# minSTMc8t6.net
KiCad netlist of a schematic drawn in EasyEDA Pro
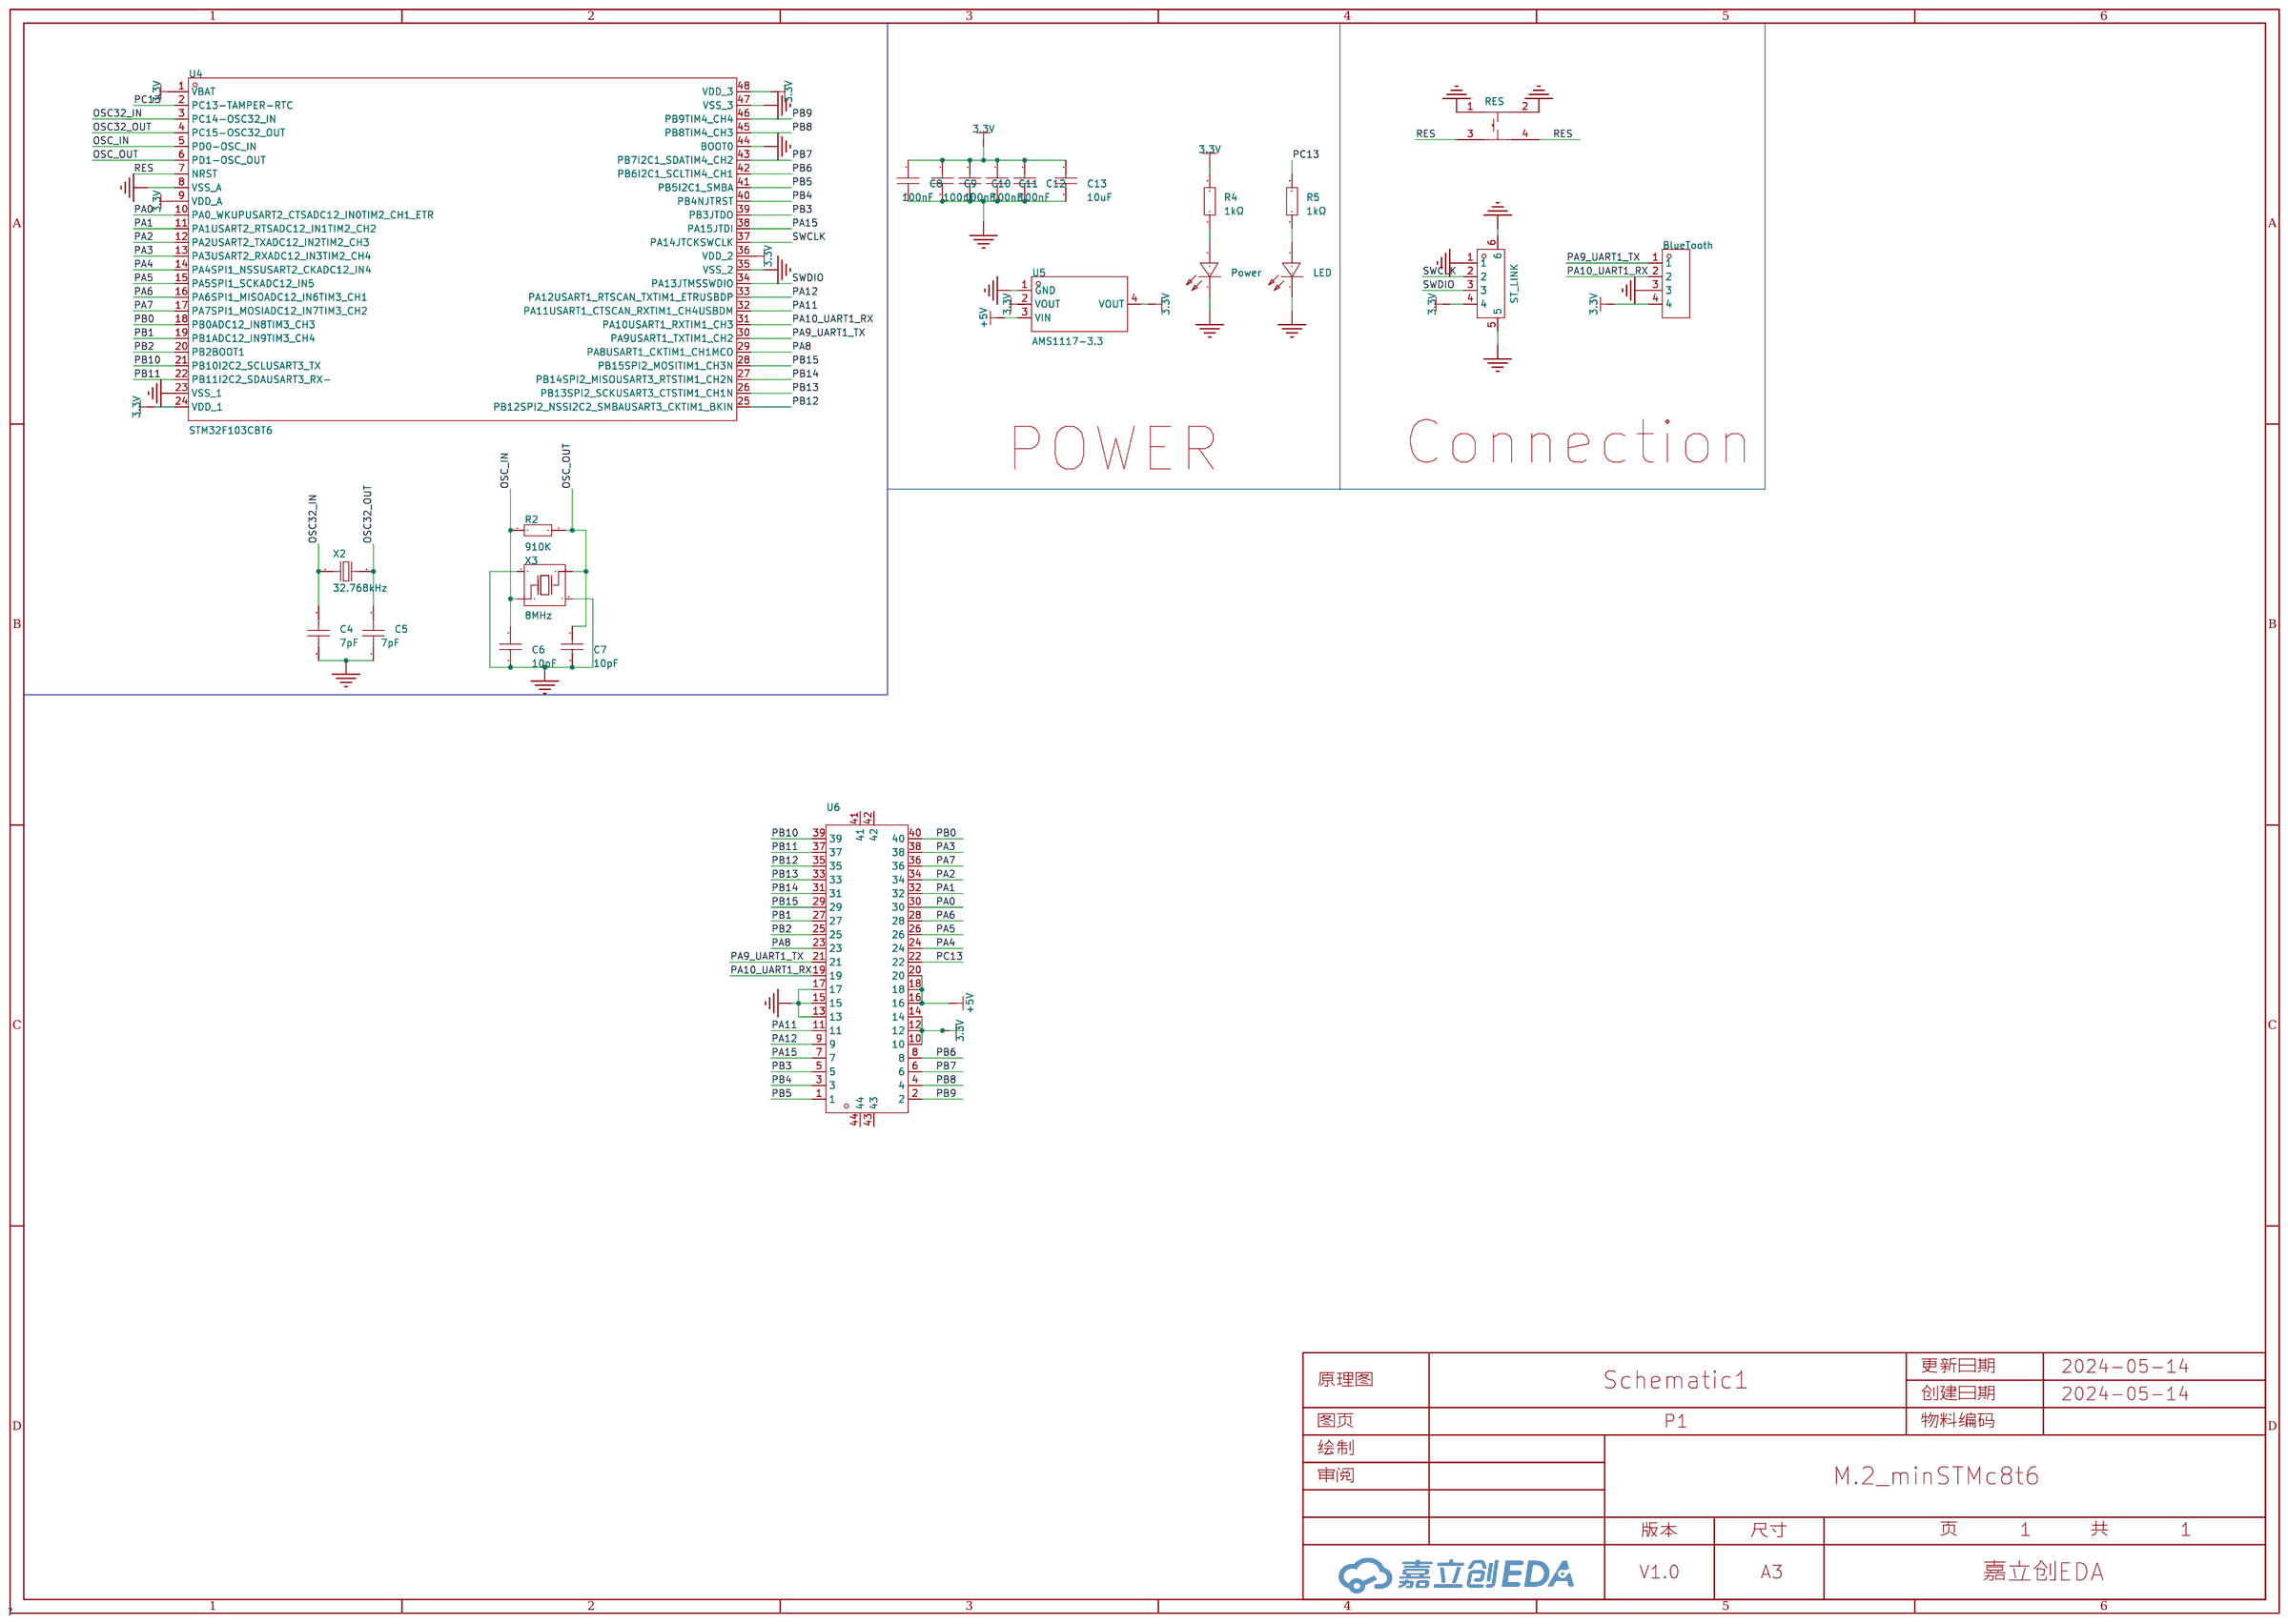
[diagram p0: schematic sheet]

(export (version "E")
  (design (tool "Eeschema 10.0.6"))
  (components
    (comp (ref "BlueTooth")
      (value "2.54-1*4P母")
      (footprint "easyedapro:HDR-TH_4P-P2.54-V-F")
      (fields (field (name "Manufacturer") "BOOMELE(博穆精密)"))
      (libsource (lib "easyedapro") (part "2.54-1*4P母"))
    )
    (comp (ref "C4")
      (value "7pF")
      (footprint "easyedapro:C0402")
      (description "容值:7pF;额定电压:50V;材质(温度系数):NP0;")
      (fields
        (field (name "Manufacturer Part") "CC0402BRNPO9BN7R0")
        (field (name "Manufacturer") "YAGEO(国巨)")
      )
      (libsource (lib "easyedapro") (part "CC0402BRNPO9BN7R0"))
    )
    (comp (ref "C5")
      (value "7pF")
      (footprint "easyedapro:C0402")
      (description "容值:7pF;额定电压:50V;材质(温度系数):NP0;")
      (fields
        (field (name "Manufacturer Part") "CC0402BRNPO9BN7R0")
        (field (name "Manufacturer") "YAGEO(国巨)")
      )
      (libsource (lib "easyedapro") (part "CC0402BRNPO9BN7R0"))
    )
    (comp (ref "C6")
      (value "10pF")
      (footprint "easyedapro:C0402")
      (description "容值:10pF;精度:±5%;额定电压:50V;材质(温度系数):NP0;")
      (fields
        (field (name "Manufacturer Part") "CC0402JRNPO9BN100")
        (field (name "Manufacturer") "YAGEO(国巨)")
      )
      (libsource (lib "easyedapro") (part "CC0402JRNPO9BN100"))
    )
    (comp (ref "C7")
      (value "10pF")
      (footprint "easyedapro:C0402")
      (description "容值:10pF;精度:±5%;额定电压:50V;材质(温度系数):NP0;")
      (fields
        (field (name "Manufacturer Part") "CC0402JRNPO9BN100")
        (field (name "Manufacturer") "YAGEO(国巨)")
      )
      (libsource (lib "easyedapro") (part "CC0402JRNPO9BN100"))
    )
    (comp (ref "C8")
      (value "100nF")
      (footprint "easyedapro:C0402")
      (description "容值:100nF;精度:±10%;额定电压:16V;材质(温度系数):X7R;")
      (fields
        (field (name "Manufacturer Part") "CL05B104KO5NNNC")
        (field (name "Manufacturer") "SAMSUNG(三星)")
      )
      (libsource (lib "easyedapro") (part "CL05B104KO5NNNC"))
    )
    (comp (ref "C9")
      (value "100nF")
      (footprint "easyedapro:C0402")
      (description "容值:100nF;精度:±10%;额定电压:16V;材质(温度系数):X7R;")
      (fields
        (field (name "Manufacturer Part") "CL05B104KO5NNNC")
        (field (name "Manufacturer") "SAMSUNG(三星)")
      )
      (libsource (lib "easyedapro") (part "CL05B104KO5NNNC"))
    )
    (comp (ref "C10")
      (value "100nF")
      (footprint "easyedapro:C0402")
      (description "容值:100nF;精度:±10%;额定电压:16V;材质(温度系数):X7R;")
      (fields
        (field (name "Manufacturer Part") "CL05B104KO5NNNC")
        (field (name "Manufacturer") "SAMSUNG(三星)")
      )
      (libsource (lib "easyedapro") (part "CL05B104KO5NNNC"))
    )
    (comp (ref "C11")
      (value "100nF")
      (footprint "easyedapro:C0402")
      (description "容值:100nF;精度:±10%;额定电压:16V;材质(温度系数):X7R;")
      (fields
        (field (name "Manufacturer Part") "CL05B104KO5NNNC")
        (field (name "Manufacturer") "SAMSUNG(三星)")
      )
      (libsource (lib "easyedapro") (part "CL05B104KO5NNNC"))
    )
    (comp (ref "C12")
      (value "100nF")
      (footprint "easyedapro:C0402")
      (description "容值:100nF;精度:±10%;额定电压:16V;材质(温度系数):X7R;")
      (fields
        (field (name "Manufacturer Part") "CL05B104KO5NNNC")
        (field (name "Manufacturer") "SAMSUNG(三星)")
      )
      (libsource (lib "easyedapro") (part "CL05B104KO5NNNC"))
    )
    (comp (ref "C13")
      (value "10uF")
      (footprint "easyedapro:C0402")
      (description "容值:10uF;精度:±20%;额定电压:6.3V;材质(温度系数):X5R;")
      (fields
        (field (name "Manufacturer Part") "CL05A106MQ5NUNC")
        (field (name "Manufacturer") "SAMSUNG(三星)")
      )
      (libsource (lib "easyedapro") (part "CL05A106MQ5NUNC"))
    )
    (comp (ref "LED")
      (value "NCD0402R1")
      (footprint "easyedapro:LED0402-RD")
      (fields (field (name "Manufacturer") "国星光电"))
      (libsource (lib "easyedapro") (part "FC-F1005HRK-620H5"))
    )
    (comp (ref "Power")
      (value "NCD0402R1")
      (footprint "easyedapro:LED0402-RD")
      (fields (field (name "Manufacturer") "国星光电"))
      (libsource (lib "easyedapro") (part "FC-F1005HRK-620H5"))
    )
    (comp (ref "R2") (value "910K") (footprint "easyedapro:R0603") (libsource (lib "easyedapro") (part "电阻")))
    (comp (ref "R4")
      (value "1kΩ")
      (footprint "easyedapro:R0402")
      (description "电阻类型:厚膜电阻;阻值:1kΩ;精度:±1%;功率:62.5mW;最大工作电压:50V;温度系数:±100ppm/°C;")
      (fields
        (field (name "Manufacturer Part") "0402WGF1001TCE")
        (field (name "Manufacturer") "UNI-ROYAL(厚声)")
      )
      (libsource (lib "easyedapro") (part "0402WGF1001TCE"))
    )
    (comp (ref "R5")
      (value "1kΩ")
      (footprint "easyedapro:R0402")
      (description "电阻类型:厚膜电阻;阻值:1kΩ;精度:±1%;功率:62.5mW;最大工作电压:50V;温度系数:±100ppm/°C;")
      (fields
        (field (name "Manufacturer Part") "0402WGF1001TCE")
        (field (name "Manufacturer") "UNI-ROYAL(厚声)")
      )
      (libsource (lib "easyedapro") (part "0402WGF1001TCE"))
    )
    (comp (ref "RES")
      (value "K2-1808SN-A3SW-01")
      (footprint "easyedapro:SW-SMD_4P-L4.2-W3.3-P2.15-LS5.1")
      (description "作用力:180gf;安装方式:立贴;开关长度:4.2mm;开关宽度:3.25mm;开关高度:2.5mm;触点电流:50mA;额定电压(DC):12V;绝缘电阻:100MΩ;机械寿命:10万次;")
      (fields (field (name "Manufacturer") "韩国韩荣"))
      (libsource (lib "easyedapro") (part "K2-1808SN-A3SW-01"))
    )
    (comp (ref "ST_LINK")
      (value "HDGC1251WR-S-4P")
      (footprint "easyedapro:CONN-SMD_4P-P1.25_HDGC-HDGC1251WR-S-4P")
      (description "插针结构:1x4P;间距:1.25mm;安装方式:卧贴;参考系列:-;总PIN数:4P;排数:1;每排PIN数:4;行距:-;额定电流:1A;工作温度范围:-25°C~+70°C;")
      (fields (field (name "Manufacturer") "HDGC(华德共创)"))
      (libsource (lib "easyedapro") (part "HDGC1251WR-S-4P"))
    )
    (comp (ref "U4")
      (value "STM32F103CBT6")
      (footprint "easyedapro:LQFP-48_L7.0-W7.0-P0.50-LS9.0-BL")
      (description "CPU内核:CM3;程序存储容量:128KB;RAM总容量:20KB;GPIO端口数量:37;工作电压范围:2V~3.6V;CPU最大主频:72MHz;程序存储器类型:FLASH;")
      (fields (field (name "Manufacturer") "ST(意法半导体)"))
      (libsource (lib "easyedapro") (part "STM32F103CBT6"))
    )
    (comp (ref "U5")
      (value "AMS1117-3.3")
      (footprint "easyedapro:SOT-223-3_L6.5-W3.4-P2.30-LS7.0-BR")
      (description "输出类型:固定;最大输入电压:-;输出电压:3.3V;最大输出电流:1A;电源纹波抑制比(PSRR):72dB@(120Hz);输出极性:正极;")
      (fields (field (name "Manufacturer") "AMS"))
      (libsource (lib "easyedapro") (part "AMS1117-3.3"))
    )
    (comp (ref "U6")
      (value "HC-PBB40C-40DP-0.4V-02")
      (footprint "easyedapro:CONN-SMD_40P-P0.40_HCTL_HC-PBB40C-40DP-0.4V-02")
      (description "PIN总数:40P;间距:0.4mm;公母:公;安装方式:立贴;行数:2;额定电流:300mA;工作温度范围:-35°C~+85°C;")
      (fields (field (name "Manufacturer") "HCTL(华灿天禄)"))
      (libsource (lib "easyedapro") (part "HC-PBB40C-40DP-0.4V-02"))
    )
    (comp (ref "X2")
      (value "32.768kHz")
      (footprint "easyedapro:FC-135R_L3.2-W1.5")
      (description "晶振类型:贴片晶振;频率:32.768kHz;常温频差:±20ppm;外接负载电容:12.5pF;")
      (fields (field (name "Manufacturer Part") "Q13FC13500004") (field (name "Manufacturer") "EPSON(爱普生)"))
      (libsource (lib "easyedapro") (part "Q13FC1350000400"))
    )
    (comp (ref "X3")
      (value "8MHz")
      (footprint "easyedapro:OSC-SMD_4P-L3.2-W2.5-BL")
      (description "晶振类型:贴片晶振;频率:8MHz;常温频差:±10ppm;外接负载电容:10pF;频率稳定度(全温):±15ppm;")
      (fields (field (name "Manufacturer Part") "TAXM8M4RDBCCT2T") (field (name "Manufacturer") "YJX(雅晶鑫)"))
      (libsource (lib "easyedapro") (part "TAXM8M4RDBCCT2T"))
    )
  )
  (nets
    (net (code "1") (name "+5V") (class "Default")
      (node (ref "U5") (pin "3") (pinfunction "VIN_3") (pintype "unspecified"))
      (node (ref "U6") (pin "16") (pinfunction "16_16") (pintype "unspecified"))
      (node (ref "U6") (pin "18") (pinfunction "18_18") (pintype "unspecified"))
      (node (ref "U6") (pin "20") (pinfunction "20_20") (pintype "unspecified"))
    )
    (net (code "2") (name "/OSC32_IN") (class "Default")
      (node (ref "C4") (pin "2") (pinfunction "2_2") (pintype "unspecified"))
      (node (ref "U4") (pin "3") (pinfunction "PC14-OSC32_IN_3") (pintype "unspecified"))
      (node (ref "X2") (pin "1") (pinfunction "1_1") (pintype "unspecified"))
    )
    (net (code "3") (name "/OSC32_OUT") (class "Default")
      (node (ref "C5") (pin "2") (pinfunction "2_2") (pintype "unspecified"))
      (node (ref "U4") (pin "4") (pinfunction "PC15-OSC32_OUT_4") (pintype "unspecified"))
      (node (ref "X2") (pin "2") (pinfunction "2_2") (pintype "unspecified"))
    )
    (net (code "4") (name "/OSC_IN") (class "Default")
      (node (ref "C6") (pin "2") (pinfunction "2_2") (pintype "input"))
      (node (ref "R2") (pin "1") (pinfunction "1_1") (pintype "input"))
      (node (ref "U4") (pin "5") (pinfunction "PD0-OSC_IN_5") (pintype "unspecified"))
      (node (ref "X3") (pin "1") (pinfunction "1_1") (pintype "input"))
    )
    (net (code "5") (name "/OSC_OUT") (class "Default")
      (node (ref "C7") (pin "2") (pinfunction "2_2") (pintype "input"))
      (node (ref "R2") (pin "2") (pinfunction "2_2") (pintype "input"))
      (node (ref "U4") (pin "6") (pinfunction "PD1-OSC_OUT_6") (pintype "unspecified"))
      (node (ref "X3") (pin "3") (pinfunction "3_3") (pintype "input"))
    )
    (net (code "6") (name "/PA0") (class "Default")
      (node (ref "U4") (pin "10") (pinfunction "PA0_WKUPUSART2_CTSADC12_IN0TIM2_CH1_ETR_10") (pintype "unspecified"))
      (node (ref "U6") (pin "30") (pinfunction "30_30") (pintype "unspecified"))
    )
    (net (code "7") (name "/PA1") (class "Default")
      (node (ref "U4") (pin "11") (pinfunction "PA1USART2_RTSADC12_IN1TIM2_CH2_11") (pintype "unspecified"))
      (node (ref "U6") (pin "32") (pinfunction "32_32") (pintype "unspecified"))
    )
    (net (code "8") (name "/PA2") (class "Default")
      (node (ref "U4") (pin "12") (pinfunction "PA2USART2_TXADC12_IN2TIM2_CH3_12") (pintype "unspecified"))
      (node (ref "U6") (pin "34") (pinfunction "34_34") (pintype "unspecified"))
    )
    (net (code "9") (name "/PA3") (class "Default")
      (node (ref "U4") (pin "13") (pinfunction "PA3USART2_RXADC12_IN3TIM2_CH4_13") (pintype "unspecified"))
      (node (ref "U6") (pin "38") (pinfunction "38_38") (pintype "unspecified"))
    )
    (net (code "10") (name "/PA4") (class "Default")
      (node (ref "U4") (pin "14") (pinfunction "PA4SPI1_NSSUSART2_CKADC12_IN4_14") (pintype "unspecified"))
      (node (ref "U6") (pin "24") (pinfunction "24_24") (pintype "unspecified"))
    )
    (net (code "11") (name "/PA5") (class "Default")
      (node (ref "U4") (pin "15") (pinfunction "PA5SPI1_SCKADC12_IN5_15") (pintype "unspecified"))
      (node (ref "U6") (pin "26") (pinfunction "26_26") (pintype "unspecified"))
    )
    (net (code "12") (name "/PA6") (class "Default")
      (node (ref "U4") (pin "16") (pinfunction "PA6SPI1_MISOADC12_IN6TIM3_CH1_16") (pintype "unspecified"))
      (node (ref "U6") (pin "28") (pinfunction "28_28") (pintype "unspecified"))
    )
    (net (code "13") (name "/PA7") (class "Default")
      (node (ref "U4") (pin "17") (pinfunction "PA7SPI1_MOSIADC12_IN7TIM3_CH2_17") (pintype "unspecified"))
      (node (ref "U6") (pin "36") (pinfunction "36_36") (pintype "unspecified"))
    )
    (net (code "14") (name "/PA8") (class "Default")
      (node (ref "U4") (pin "29") (pinfunction "PA8USART1_CKTIM1_CH1MCO_29") (pintype "unspecified"))
      (node (ref "U6") (pin "23") (pinfunction "23_23") (pintype "unspecified"))
    )
    (net (code "15") (name "/PA9_UART1_TX") (class "Default")
      (node (ref "BlueTooth") (pin "1") (pinfunction "1_1") (pintype "unspecified"))
      (node (ref "U4") (pin "30") (pinfunction "PA9USART1_TXTIM1_CH2_30") (pintype "unspecified"))
      (node (ref "U6") (pin "21") (pinfunction "21_21") (pintype "unspecified"))
    )
    (net (code "16") (name "/PA10_UART1_RX") (class "Default")
      (node (ref "BlueTooth") (pin "2") (pinfunction "2_2") (pintype "unspecified"))
      (node (ref "U4") (pin "31") (pinfunction "PA10USART1_RXTIM1_CH3_31") (pintype "unspecified"))
      (node (ref "U6") (pin "19") (pinfunction "19_19") (pintype "unspecified"))
    )
    (net (code "17") (name "/PA11") (class "Default")
      (node (ref "U4") (pin "32") (pinfunction "PA11USART1_CTSCAN_RXTIM1_CH4USBDM_32") (pintype "unspecified"))
      (node (ref "U6") (pin "11") (pinfunction "11_11") (pintype "unspecified"))
    )
    (net (code "18") (name "/PA12") (class "Default")
      (node (ref "U4") (pin "33") (pinfunction "PA12USART1_RTSCAN_TXTIM1_ETRUSBDP_33") (pintype "unspecified"))
      (node (ref "U6") (pin "9") (pinfunction "9_9") (pintype "unspecified"))
    )
    (net (code "19") (name "/PA15") (class "Default")
      (node (ref "U4") (pin "38") (pinfunction "PA15JTDI_38") (pintype "unspecified"))
      (node (ref "U6") (pin "7") (pinfunction "7_7") (pintype "unspecified"))
    )
    (net (code "20") (name "/PB0") (class "Default")
      (node (ref "U4") (pin "18") (pinfunction "PB0ADC12_IN8TIM3_CH3_18") (pintype "unspecified"))
      (node (ref "U6") (pin "40") (pinfunction "40_40") (pintype "unspecified"))
    )
    (net (code "21") (name "/PB1") (class "Default")
      (node (ref "U4") (pin "19") (pinfunction "PB1ADC12_IN9TIM3_CH4_19") (pintype "unspecified"))
      (node (ref "U6") (pin "27") (pinfunction "27_27") (pintype "unspecified"))
    )
    (net (code "22") (name "/PB2") (class "Default")
      (node (ref "U4") (pin "20") (pinfunction "PB2BOOT1_20") (pintype "unspecified"))
      (node (ref "U6") (pin "25") (pinfunction "25_25") (pintype "unspecified"))
    )
    (net (code "23") (name "/PB3") (class "Default")
      (node (ref "U4") (pin "39") (pinfunction "PB3JTDO_39") (pintype "unspecified"))
      (node (ref "U6") (pin "5") (pinfunction "5_5") (pintype "unspecified"))
    )
    (net (code "24") (name "/PB4") (class "Default")
      (node (ref "U4") (pin "40") (pinfunction "PB4NJTRST_40") (pintype "unspecified"))
      (node (ref "U6") (pin "3") (pinfunction "3_3") (pintype "unspecified"))
    )
    (net (code "25") (name "/PB5") (class "Default")
      (node (ref "U4") (pin "41") (pinfunction "PB5I2C1_SMBA_41") (pintype "unspecified"))
      (node (ref "U6") (pin "1") (pinfunction "1_1") (pintype "unspecified"))
    )
    (net (code "26") (name "/PB6") (class "Default")
      (node (ref "U4") (pin "42") (pinfunction "PB6I2C1_SCLTIM4_CH1_42") (pintype "unspecified"))
      (node (ref "U6") (pin "8") (pinfunction "8_8") (pintype "unspecified"))
    )
    (net (code "27") (name "/PB7") (class "Default")
      (node (ref "U4") (pin "43") (pinfunction "PB7I2C1_SDATIM4_CH2_43") (pintype "unspecified"))
      (node (ref "U6") (pin "6") (pinfunction "6_6") (pintype "unspecified"))
    )
    (net (code "28") (name "/PB8") (class "Default")
      (node (ref "U4") (pin "45") (pinfunction "PB8TIM4_CH3_45") (pintype "unspecified"))
      (node (ref "U6") (pin "4") (pinfunction "4_4") (pintype "unspecified"))
    )
    (net (code "29") (name "/PB9") (class "Default")
      (node (ref "U4") (pin "46") (pinfunction "PB9TIM4_CH4_46") (pintype "unspecified"))
      (node (ref "U6") (pin "2") (pinfunction "2_2") (pintype "unspecified"))
    )
    (net (code "30") (name "/PB10") (class "Default")
      (node (ref "U4") (pin "21") (pinfunction "PB10I2C2_SCLUSART3_TX_21") (pintype "unspecified"))
      (node (ref "U6") (pin "39") (pinfunction "39_39") (pintype "unspecified"))
    )
    (net (code "31") (name "/PB11") (class "Default")
      (node (ref "U4") (pin "22") (pinfunction "PB11I2C2_SDAUSART3_RX-_22") (pintype "unspecified"))
      (node (ref "U6") (pin "37") (pinfunction "37_37") (pintype "unspecified"))
    )
    (net (code "32") (name "/PB12") (class "Default")
      (node (ref "U4") (pin "25") (pinfunction "PB12SPI2_NSSI2C2_SMBAUSART3_CKTIM1_BKIN_25") (pintype "unspecified"))
      (node (ref "U6") (pin "35") (pinfunction "35_35") (pintype "unspecified"))
    )
    (net (code "33") (name "/PB13") (class "Default")
      (node (ref "U4") (pin "26") (pinfunction "PB13SPI2_SCKUSART3_CTSTIM1_CH1N_26") (pintype "unspecified"))
      (node (ref "U6") (pin "33") (pinfunction "33_33") (pintype "unspecified"))
    )
    (net (code "34") (name "/PB14") (class "Default")
      (node (ref "U4") (pin "27") (pinfunction "PB14SPI2_MISOUSART3_RTSTIM1_CH2N_27") (pintype "unspecified"))
      (node (ref "U6") (pin "31") (pinfunction "31_31") (pintype "unspecified"))
    )
    (net (code "35") (name "/PB15") (class "Default")
      (node (ref "U4") (pin "28") (pinfunction "PB15SPI2_MOSITIM1_CH3N_28") (pintype "unspecified"))
      (node (ref "U6") (pin "29") (pinfunction "29_29") (pintype "unspecified"))
    )
    (net (code "36") (name "/PC13") (class "Default")
      (node (ref "R5") (pin "2") (pinfunction "2_2") (pintype "input"))
      (node (ref "U4") (pin "2") (pinfunction "PC13-TAMPER-RTC_2") (pintype "unspecified"))
      (node (ref "U6") (pin "22") (pinfunction "22_22") (pintype "unspecified"))
    )
    (net (code "37") (name "/RES") (class "Default")
      (node (ref "RES") (pin "3") (pinfunction "3_3") (pintype "input"))
      (node (ref "RES") (pin "4") (pinfunction "4_4") (pintype "input"))
      (node (ref "U4") (pin "7") (pinfunction "NRST_7") (pintype "unspecified"))
    )
    (net (code "38") (name "/SWCLK") (class "Default")
      (node (ref "ST_LINK") (pin "2") (pinfunction "2_2") (pintype "unspecified"))
      (node (ref "U4") (pin "37") (pinfunction "PA14JTCKSWCLK_37") (pintype "unspecified"))
    )
    (net (code "39") (name "/SWDIO") (class "Default")
      (node (ref "ST_LINK") (pin "3") (pinfunction "3_3") (pintype "unspecified"))
      (node (ref "U4") (pin "34") (pinfunction "PA13JTMSSWDIO_34") (pintype "unspecified"))
    )
    (net (code "40") (name "3.3V") (class "Default")
      (node (ref "BlueTooth") (pin "4") (pinfunction "4_4") (pintype "unspecified"))
      (node (ref "C10") (pin "2") (pinfunction "2_2") (pintype "input"))
      (node (ref "C11") (pin "2") (pinfunction "2_2") (pintype "input"))
      (node (ref "C12") (pin "2") (pinfunction "2_2") (pintype "input"))
      (node (ref "C13") (pin "2") (pinfunction "2_2") (pintype "input"))
      (node (ref "C8") (pin "2") (pinfunction "2_2") (pintype "input"))
      (node (ref "C9") (pin "2") (pinfunction "2_2") (pintype "input"))
      (node (ref "R4") (pin "2") (pinfunction "2_2") (pintype "input"))
      (node (ref "ST_LINK") (pin "4") (pinfunction "4_4") (pintype "unspecified"))
      (node (ref "U4") (pin "1") (pinfunction "VBAT_1") (pintype "unspecified"))
      (node (ref "U4") (pin "24") (pinfunction "VDD_1_24") (pintype "unspecified"))
      (node (ref "U4") (pin "36") (pinfunction "VDD_2_36") (pintype "unspecified"))
      (node (ref "U4") (pin "48") (pinfunction "VDD_3_48") (pintype "unspecified"))
      (node (ref "U4") (pin "9") (pinfunction "VDD_A_9") (pintype "unspecified"))
      (node (ref "U5") (pin "2") (pinfunction "VOUT_2") (pintype "unspecified"))
      (node (ref "U5") (pin "4") (pinfunction "VOUT_4") (pintype "unspecified"))
      (node (ref "U6") (pin "10") (pinfunction "10_10") (pintype "unspecified"))
      (node (ref "U6") (pin "12") (pinfunction "12_12") (pintype "unspecified"))
      (node (ref "U6") (pin "14") (pinfunction "14_14") (pintype "unspecified"))
    )
    (net (code "41") (name "GND") (class "Default")
      (node (ref "BlueTooth") (pin "3") (pinfunction "3_3") (pintype "unspecified"))
      (node (ref "C10") (pin "1") (pinfunction "1_1") (pintype "input"))
      (node (ref "C11") (pin "1") (pinfunction "1_1") (pintype "input"))
      (node (ref "C12") (pin "1") (pinfunction "1_1") (pintype "input"))
      (node (ref "C13") (pin "1") (pinfunction "1_1") (pintype "input"))
      (node (ref "C4") (pin "1") (pinfunction "1_1") (pintype "unspecified"))
      (node (ref "C5") (pin "1") (pinfunction "1_1") (pintype "unspecified"))
      (node (ref "C6") (pin "1") (pinfunction "1_1") (pintype "input"))
      (node (ref "C7") (pin "1") (pinfunction "1_1") (pintype "input"))
      (node (ref "C8") (pin "1") (pinfunction "1_1") (pintype "input"))
      (node (ref "C9") (pin "1") (pinfunction "1_1") (pintype "input"))
      (node (ref "LED") (pin "1") (pinfunction "K_1") (pintype "unspecified"))
      (node (ref "Power") (pin "1") (pinfunction "K_1") (pintype "unspecified"))
      (node (ref "RES") (pin "1") (pinfunction "1_1") (pintype "input"))
      (node (ref "RES") (pin "2") (pinfunction "2_2") (pintype "input"))
      (node (ref "ST_LINK") (pin "1") (pinfunction "1_1") (pintype "unspecified"))
      (node (ref "ST_LINK") (pin "5") (pinfunction "5_5") (pintype "unspecified"))
      (node (ref "ST_LINK") (pin "6") (pinfunction "6_6") (pintype "unspecified"))
      (node (ref "U4") (pin "23") (pinfunction "VSS_1_23") (pintype "unspecified"))
      (node (ref "U4") (pin "35") (pinfunction "VSS_2_35") (pintype "unspecified"))
      (node (ref "U4") (pin "44") (pinfunction "BOOT0_44") (pintype "unspecified"))
      (node (ref "U4") (pin "47") (pinfunction "VSS_3_47") (pintype "unspecified"))
      (node (ref "U4") (pin "8") (pinfunction "VSS_A_8") (pintype "unspecified"))
      (node (ref "U5") (pin "1") (pinfunction "GND_1") (pintype "unspecified"))
      (node (ref "U6") (pin "13") (pinfunction "13_13") (pintype "unspecified"))
      (node (ref "U6") (pin "15") (pinfunction "15_15") (pintype "unspecified"))
      (node (ref "U6") (pin "17") (pinfunction "17_17") (pintype "unspecified"))
      (node (ref "X3") (pin "2") (pinfunction "2_2") (pintype "input"))
      (node (ref "X3") (pin "4") (pinfunction "4_4") (pintype "input"))
    )
    (net (code "42") (name "Net-(LED-A)") (class "Default")
      (node (ref "LED") (pin "2") (pinfunction "A_2") (pintype "unspecified"))
      (node (ref "R5") (pin "1") (pinfunction "1_1") (pintype "input"))
    )
    (net (code "43") (name "Net-(Power-A)") (class "Default")
      (node (ref "Power") (pin "2") (pinfunction "A_2") (pintype "unspecified"))
      (node (ref "R4") (pin "1") (pinfunction "1_1") (pintype "input"))
    )
    (net (code "44") (name "unconnected-(U6-Pad41)") (class "Default")
      (node (ref "U6") (pin "41") (pinfunction "41_41") (pintype "unspecified"))
    )
    (net (code "45") (name "unconnected-(U6-Pad42)") (class "Default")
      (node (ref "U6") (pin "42") (pinfunction "42_42") (pintype "unspecified"))
    )
    (net (code "46") (name "unconnected-(U6-Pad43)") (class "Default")
      (node (ref "U6") (pin "43") (pinfunction "43_43") (pintype "unspecified"))
    )
    (net (code "47") (name "unconnected-(U6-Pad44)") (class "Default")
      (node (ref "U6") (pin "44") (pinfunction "44_44") (pintype "unspecified"))
    )
  )
)
